# sonoff_DIY_3_gang_Dip_version-V_1_2.net
KiCad netlist of a schematic drawn in EAGLE
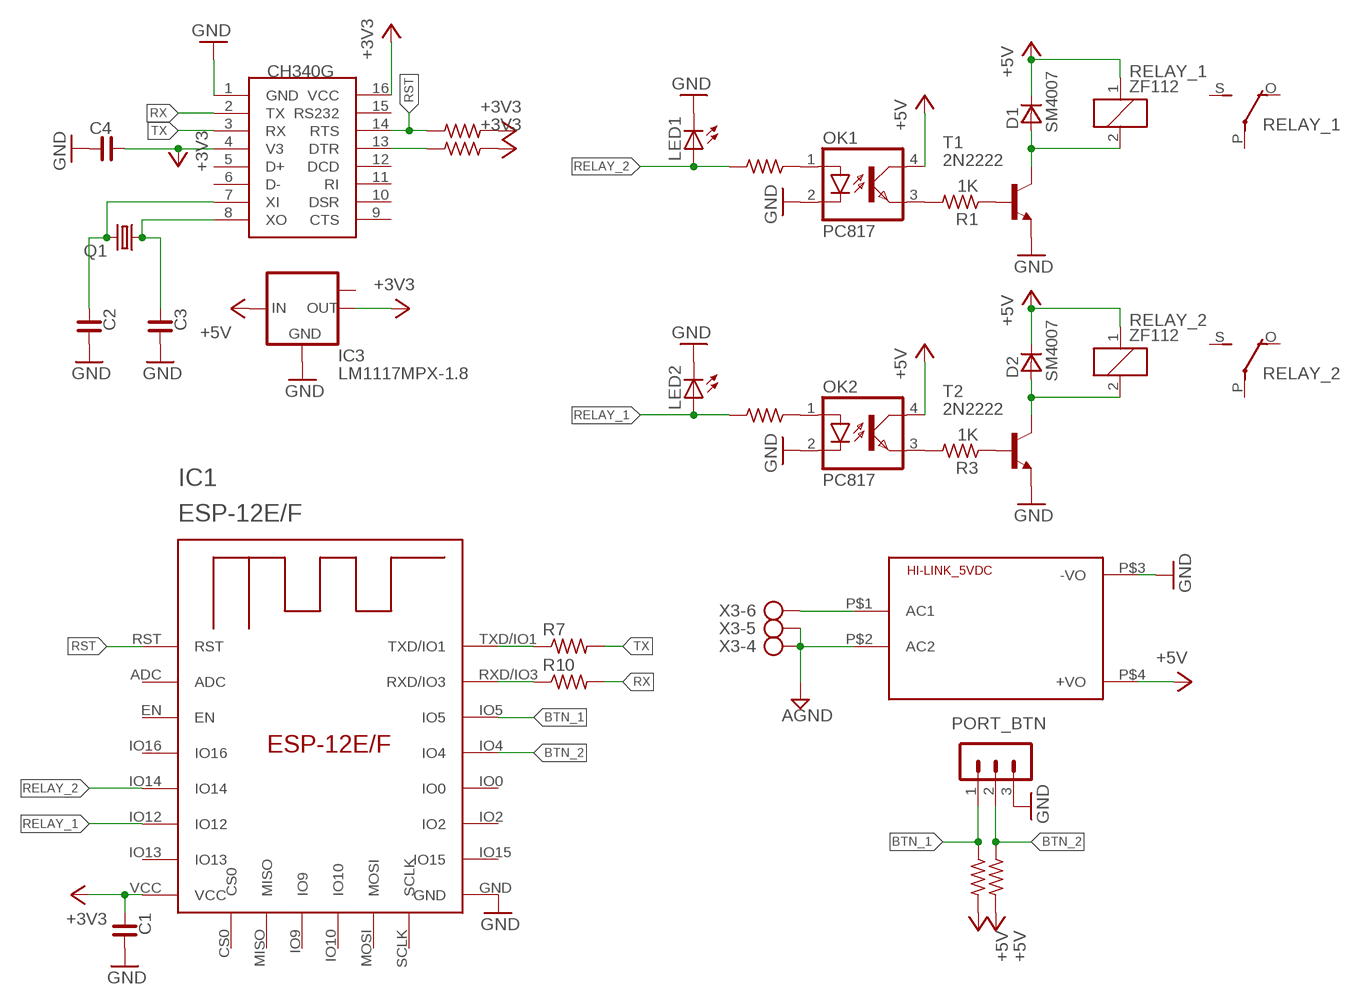
[diagram p0: schematic, sheet 1]

(export (version "E")
  (design (tool "Eeschema 10.0.6"))
  (components
    (comp (ref "C1")
      (value "C_0805")
      (footprint "eagle-import:C0805")
      (libsource (lib "eagle-import") (part "C_0805"))
    )
    (comp (ref "C2")
      (value "C_0805")
      (footprint "eagle-import:C0805")
      (libsource (lib "eagle-import") (part "C_0805"))
    )
    (comp (ref "C3")
      (value "C_0805")
      (footprint "eagle-import:C0805")
      (libsource (lib "eagle-import") (part "C_0805"))
    )
    (comp (ref "C4")
      (value "C_0805")
      (footprint "eagle-import:C0805")
      (libsource (lib "eagle-import") (part "C_0805"))
    )
    (comp (ref "D1")
      (value "SM4007")
      (footprint "eagle-import:MELF-MLL41")
      (libsource (lib "eagle-import") (part "SM4007"))
    )
    (comp (ref "D2")
      (value "SM4007")
      (footprint "eagle-import:MELF-MLL41")
      (libsource (lib "eagle-import") (part "SM4007"))
    )
    (comp (ref "HI-LINK_5VDC")
      (value "HLK-PM013W")
      (footprint "eagle-import:HLK-PM01")
      (libsource (lib "eagle-import") (part "HLK-PM013W"))
    )
    (comp (ref "IC1")
      (value "ESP-12E/F")
      (footprint "eagle-import:ESP-12E")
      (libsource (lib "eagle-import") (part "ESP-12E/F"))
    )
    (comp (ref "IC3")
      (value "LM1117MPX-1.8")
      (footprint "eagle-import:SOT223")
      (libsource (lib "eagle-import") (part "LM1117MPX-1.8"))
    )
    (comp (ref "LED1")
      (value "LED3MM")
      (footprint "eagle-import:LED3MM")
      (libsource (lib "eagle-import") (part "LED3MM"))
    )
    (comp (ref "LED2")
      (value "LED3MM")
      (footprint "eagle-import:LED3MM")
      (libsource (lib "eagle-import") (part "LED3MM"))
    )
    (comp (ref "OK1")
      (value "PC817")
      (footprint "eagle-import:DIL04")
      (fields (field (name "MPN") "PC817X4J000F"))
      (libsource (lib "eagle-import") (part "PC817"))
    )
    (comp (ref "OK2")
      (value "PC817")
      (footprint "eagle-import:DIL04")
      (fields (field (name "MPN") "PC817X4J000F"))
      (libsource (lib "eagle-import") (part "PC817"))
    )
    (comp (ref "PORT_BTN")
      (value "MA03-1")
      (footprint "eagle-import:MA03-1")
      (libsource (lib "eagle-import") (part "MA03-1"))
    )
    (comp (ref "Q1")
      (value "CRYSTALHC18U-V")
      (footprint "eagle-import:HC18U-V")
      (libsource (lib "eagle-import") (part "CRYSTALHC18U-V"))
    )
    (comp (ref "R1")
      (value "1K")
      (footprint "eagle-import:R0805")
      (libsource (lib "eagle-import") (part "R_0805"))
    )
    (comp (ref "R2")
      (value "1K")
      (footprint "eagle-import:R0805")
      (libsource (lib "eagle-import") (part "R_0805"))
    )
    (comp (ref "R3")
      (value "1K")
      (footprint "eagle-import:R0805")
      (libsource (lib "eagle-import") (part "R_0805"))
    )
    (comp (ref "R4")
      (value "1K")
      (footprint "eagle-import:R0805")
      (libsource (lib "eagle-import") (part "R_0805"))
    )
    (comp (ref "R5")
      (value "1K")
      (footprint "eagle-import:R0805")
      (libsource (lib "eagle-import") (part "R_0805"))
    )
    (comp (ref "R6")
      (value "1K")
      (footprint "eagle-import:R0805")
      (libsource (lib "eagle-import") (part "R_0805"))
    )
    (comp (ref "R7")
      (value "R-US_0207/10")
      (footprint "eagle-import:0207_10")
      (libsource (lib "eagle-import") (part "R-US_0207/10"))
    )
    (comp (ref "R8")
      (value "1K")
      (footprint "eagle-import:R0805")
      (libsource (lib "eagle-import") (part "R_0805"))
    )
    (comp (ref "R9")
      (value "1K")
      (footprint "eagle-import:R0805")
      (libsource (lib "eagle-import") (part "R_0805"))
    )
    (comp (ref "R10")
      (value "R-US_0207/10")
      (footprint "eagle-import:0207_10")
      (libsource (lib "eagle-import") (part "R-US_0207/10"))
    )
    (comp (ref "RELAY_1")
      (value "ZF112")
      (footprint "eagle-import:ZF112")
      (libsource (lib "eagle-import") (part "ZF112"))
    )
    (comp (ref "RELAY_2")
      (value "ZF112")
      (footprint "eagle-import:ZF112")
      (libsource (lib "eagle-import") (part "ZF112"))
    )
    (comp (ref "T1")
      (value "2N2222")
      (footprint "eagle-import:TO18")
      (libsource (lib "eagle-import") (part "2N2222"))
    )
    (comp (ref "T2")
      (value "2N2222")
      (footprint "eagle-import:TO18")
      (libsource (lib "eagle-import") (part "2N2222"))
    )
    (comp (ref "U$1")
      (value "CH340G")
      (footprint "eagle-import:SOIC16")
      (libsource (lib "eagle-import") (part "CH340G"))
    )
    (comp (ref "X3")
      (value "SMKDSP_1,5/6")
      (footprint "eagle-import:SMKDSP_1,5_6")
      (fields (field (name "MF") "FARNELL") (field (name "MPN") "1733619"))
      (libsource (lib "eagle-import") (part "SMKDSP_1,5/6"))
    )
  )
  (nets
    (net (code "1") (name "+3V3") (class "Default")
      (node (ref "C1") (pin "2") (pinfunction "2_2") (pintype "passive"))
      (node (ref "C4") (pin "1") (pinfunction "1_1") (pintype "passive"))
      (node (ref "IC1") (pin "VCC") (pinfunction "VCC_VCC") (pintype "power_in"))
      (node (ref "IC3") (pin "2") (pinfunction "OUT_2") (pintype "passive"))
      (node (ref "R8") (pin "1") (pinfunction "1_1") (pintype "passive"))
      (node (ref "R9") (pin "1") (pinfunction "1_1") (pintype "passive"))
      (node (ref "U$1") (pin "16") (pinfunction "VCC_16") (pintype "bidirectional"))
      (node (ref "U$1") (pin "4") (pinfunction "V3_4") (pintype "bidirectional"))
    )
    (net (code "2") (name "+5V") (class "Default")
      (node (ref "D1") (pin "C") (pinfunction "C_C") (pintype "passive"))
      (node (ref "D2") (pin "C") (pinfunction "C_C") (pintype "passive"))
      (node (ref "HI-LINK_5VDC") (pin "P$4") (pinfunction "+VO_P$4") (pintype "bidirectional"))
      (node (ref "IC3") (pin "3") (pinfunction "IN_3") (pintype "input"))
      (node (ref "OK1") (pin "4") (pinfunction "COL_4") (pintype "passive"))
      (node (ref "OK2") (pin "4") (pinfunction "COL_4") (pintype "passive"))
      (node (ref "R5") (pin "2") (pinfunction "2_2") (pintype "passive"))
      (node (ref "R6") (pin "2") (pinfunction "2_2") (pintype "passive"))
      (node (ref "RELAY_1") (pin "1") (pinfunction "1_1") (pintype "passive"))
      (node (ref "RELAY_2") (pin "1") (pinfunction "1_1") (pintype "passive"))
    )
    (net (code "3") (name "AGND") (class "Default")
      (node (ref "HI-LINK_5VDC") (pin "P$2") (pinfunction "AC2_P$2") (pintype "bidirectional"))
      (node (ref "X3") (pin "4") (pinfunction "KL_4") (pintype "passive"))
      (node (ref "X3") (pin "5") (pinfunction "KL_5") (pintype "passive"))
    )
    (net (code "4") (name "BTN_1") (class "Default")
      (node (ref "IC1") (pin "IO5") (pinfunction "IO5_IO5") (pintype "bidirectional"))
      (node (ref "PORT_BTN") (pin "1") (pinfunction "1_1") (pintype "passive"))
      (node (ref "R5") (pin "1") (pinfunction "1_1") (pintype "passive"))
    )
    (net (code "5") (name "BTN_2") (class "Default")
      (node (ref "IC1") (pin "IO4") (pinfunction "IO4_IO4") (pintype "bidirectional"))
      (node (ref "PORT_BTN") (pin "2") (pinfunction "2_2") (pintype "passive"))
      (node (ref "R6") (pin "1") (pinfunction "1_1") (pintype "passive"))
    )
    (net (code "6") (name "GND") (class "Default")
      (node (ref "C1") (pin "1") (pinfunction "1_1") (pintype "passive"))
      (node (ref "C2") (pin "1") (pinfunction "1_1") (pintype "passive"))
      (node (ref "C3") (pin "1") (pinfunction "1_1") (pintype "passive"))
      (node (ref "C4") (pin "2") (pinfunction "2_2") (pintype "passive"))
      (node (ref "HI-LINK_5VDC") (pin "P$3") (pinfunction "-VO_P$3") (pintype "bidirectional"))
      (node (ref "IC1") (pin "GND") (pinfunction "GND_GND") (pintype "power_in"))
      (node (ref "IC3") (pin "1") (pinfunction "GND_1") (pintype "input"))
      (node (ref "LED1") (pin "K") (pinfunction "C_K") (pintype "passive"))
      (node (ref "LED2") (pin "K") (pinfunction "C_K") (pintype "passive"))
      (node (ref "OK1") (pin "2") (pinfunction "C_2") (pintype "passive"))
      (node (ref "OK2") (pin "2") (pinfunction "C_2") (pintype "passive"))
      (node (ref "PORT_BTN") (pin "3") (pinfunction "3_3") (pintype "passive"))
      (node (ref "T1") (pin "1") (pinfunction "E_1") (pintype "passive"))
      (node (ref "T2") (pin "1") (pinfunction "E_1") (pintype "passive"))
      (node (ref "U$1") (pin "1") (pinfunction "GND_1") (pintype "bidirectional"))
    )
    (net (code "7") (name "Net-(HI-LINK_5VDC-AC1)") (class "Default")
      (node (ref "HI-LINK_5VDC") (pin "P$1") (pinfunction "AC1_P$1") (pintype "bidirectional"))
      (node (ref "X3") (pin "6") (pinfunction "KL_6") (pintype "passive"))
    )
    (net (code "8") (name "Net-(IC1-PadRXD{slash}IO3)") (class "Default")
      (node (ref "IC1") (pin "RXD/IO3") (pinfunction "RXD/IO3_RXD/IO3") (pintype "bidirectional"))
      (node (ref "R10") (pin "1") (pinfunction "1_1") (pintype "passive"))
    )
    (net (code "9") (name "Net-(IC1-PadTXD{slash}IO1)") (class "Default")
      (node (ref "IC1") (pin "TXD/IO1") (pinfunction "TXD/IO1_TXD/IO1") (pintype "bidirectional"))
      (node (ref "R7") (pin "1") (pinfunction "1_1") (pintype "passive"))
    )
    (net (code "10") (name "Net-(OK1-A)") (class "Default")
      (node (ref "OK1") (pin "1") (pinfunction "A_1") (pintype "passive"))
      (node (ref "R2") (pin "1") (pinfunction "1_1") (pintype "passive"))
    )
    (net (code "11") (name "Net-(OK1-EMIT)") (class "Default")
      (node (ref "OK1") (pin "3") (pinfunction "EMIT_3") (pintype "passive"))
      (node (ref "R1") (pin "2") (pinfunction "2_2") (pintype "passive"))
    )
    (net (code "12") (name "Net-(OK2-A)") (class "Default")
      (node (ref "OK2") (pin "1") (pinfunction "A_1") (pintype "passive"))
      (node (ref "R4") (pin "1") (pinfunction "1_1") (pintype "passive"))
    )
    (net (code "13") (name "Net-(OK2-EMIT)") (class "Default")
      (node (ref "OK2") (pin "3") (pinfunction "EMIT_3") (pintype "passive"))
      (node (ref "R3") (pin "2") (pinfunction "2_2") (pintype "passive"))
    )
    (net (code "14") (name "Net-(T1-B)") (class "Default")
      (node (ref "R1") (pin "1") (pinfunction "1_1") (pintype "passive"))
      (node (ref "T1") (pin "2") (pinfunction "B_2") (pintype "passive"))
    )
    (net (code "15") (name "Net-(T1-C)") (class "Default")
      (node (ref "D1") (pin "A") (pinfunction "A_A") (pintype "passive"))
      (node (ref "RELAY_1") (pin "2") (pinfunction "2_2") (pintype "passive"))
      (node (ref "T1") (pin "3") (pinfunction "C_3") (pintype "passive"))
    )
    (net (code "16") (name "Net-(T2-B)") (class "Default")
      (node (ref "R3") (pin "1") (pinfunction "1_1") (pintype "passive"))
      (node (ref "T2") (pin "2") (pinfunction "B_2") (pintype "passive"))
    )
    (net (code "17") (name "Net-(T2-C)") (class "Default")
      (node (ref "D2") (pin "A") (pinfunction "A_A") (pintype "passive"))
      (node (ref "RELAY_2") (pin "2") (pinfunction "2_2") (pintype "passive"))
      (node (ref "T2") (pin "3") (pinfunction "C_3") (pintype "passive"))
    )
    (net (code "18") (name "Net-(U$1-DTR)") (class "Default")
      (node (ref "R9") (pin "2") (pinfunction "2_2") (pintype "passive"))
      (node (ref "U$1") (pin "13") (pinfunction "DTR_13") (pintype "bidirectional"))
    )
    (net (code "19") (name "Net-(U$1-XI)") (class "Default")
      (node (ref "C2") (pin "2") (pinfunction "2_2") (pintype "passive"))
      (node (ref "Q1") (pin "2") (pinfunction "2_2") (pintype "passive"))
      (node (ref "U$1") (pin "7") (pinfunction "XI_7") (pintype "bidirectional"))
    )
    (net (code "20") (name "Net-(U$1-XO)") (class "Default")
      (node (ref "C3") (pin "2") (pinfunction "2_2") (pintype "passive"))
      (node (ref "Q1") (pin "1") (pinfunction "1_1") (pintype "passive"))
      (node (ref "U$1") (pin "8") (pinfunction "XO_8") (pintype "bidirectional"))
    )
    (net (code "21") (name "RELAY_1") (class "Default")
      (node (ref "IC1") (pin "IO12") (pinfunction "IO12_IO12") (pintype "bidirectional"))
      (node (ref "LED2") (pin "A") (pinfunction "A_A") (pintype "passive"))
      (node (ref "R4") (pin "2") (pinfunction "2_2") (pintype "passive"))
    )
    (net (code "22") (name "RELAY_2") (class "Default")
      (node (ref "IC1") (pin "IO14") (pinfunction "IO14_IO14") (pintype "bidirectional"))
      (node (ref "LED1") (pin "A") (pinfunction "A_A") (pintype "passive"))
      (node (ref "R2") (pin "2") (pinfunction "2_2") (pintype "passive"))
    )
    (net (code "23") (name "RST") (class "Default")
      (node (ref "IC1") (pin "RST") (pinfunction "RST_RST") (pintype "input"))
      (node (ref "R8") (pin "2") (pinfunction "2_2") (pintype "passive"))
      (node (ref "U$1") (pin "14") (pinfunction "RTS_14") (pintype "bidirectional"))
    )
    (net (code "24") (name "RX") (class "Default")
      (node (ref "R10") (pin "2") (pinfunction "2_2") (pintype "passive"))
      (node (ref "U$1") (pin "2") (pinfunction "TX_2") (pintype "bidirectional"))
    )
    (net (code "25") (name "TX") (class "Default")
      (node (ref "R7") (pin "2") (pinfunction "2_2") (pintype "passive"))
      (node (ref "U$1") (pin "3") (pinfunction "RX_3") (pintype "bidirectional"))
    )
    (net (code "26") (name "unconnected-(IC1-PadADC)") (class "Default")
      (node (ref "IC1") (pin "ADC") (pinfunction "ADC_ADC") (pintype "bidirectional"))
    )
    (net (code "27") (name "unconnected-(IC1-PadCS0)") (class "Default")
      (node (ref "IC1") (pin "CS0") (pinfunction "CS0_CS0") (pintype "bidirectional"))
    )
    (net (code "28") (name "unconnected-(IC1-PadEN)") (class "Default")
      (node (ref "IC1") (pin "EN") (pinfunction "EN_EN") (pintype "bidirectional"))
    )
    (net (code "29") (name "unconnected-(IC1-PadIO0)") (class "Default")
      (node (ref "IC1") (pin "IO0") (pinfunction "IO0_IO0") (pintype "bidirectional"))
    )
    (net (code "30") (name "unconnected-(IC1-PadIO2)") (class "Default")
      (node (ref "IC1") (pin "IO2") (pinfunction "IO2_IO2") (pintype "bidirectional"))
    )
    (net (code "31") (name "unconnected-(IC1-PadIO9)") (class "Default")
      (node (ref "IC1") (pin "IO9") (pinfunction "IO9_IO9") (pintype "bidirectional"))
    )
    (net (code "32") (name "unconnected-(IC1-PadIO10)") (class "Default")
      (node (ref "IC1") (pin "IO10") (pinfunction "IO10_IO10") (pintype "bidirectional"))
    )
    (net (code "33") (name "unconnected-(IC1-PadIO13)") (class "Default")
      (node (ref "IC1") (pin "IO13") (pinfunction "IO13_IO13") (pintype "bidirectional"))
    )
    (net (code "34") (name "unconnected-(IC1-PadIO15)") (class "Default")
      (node (ref "IC1") (pin "IO15") (pinfunction "IO15_IO15") (pintype "bidirectional"))
    )
    (net (code "35") (name "unconnected-(IC1-PadIO16)") (class "Default")
      (node (ref "IC1") (pin "IO16") (pinfunction "IO16_IO16") (pintype "bidirectional"))
    )
    (net (code "36") (name "unconnected-(IC1-PadMISO)") (class "Default")
      (node (ref "IC1") (pin "MISO") (pinfunction "MISO_MISO") (pintype "bidirectional"))
    )
    (net (code "37") (name "unconnected-(IC1-PadMOSI)") (class "Default")
      (node (ref "IC1") (pin "MOSI") (pinfunction "MOSI_MOSI") (pintype "bidirectional"))
    )
    (net (code "38") (name "unconnected-(IC1-PadSCLK)") (class "Default")
      (node (ref "IC1") (pin "SCLK") (pinfunction "SCLK_SCLK") (pintype "bidirectional"))
    )
    (net (code "39") (name "unconnected-(IC3-OUT1-PadTAB)") (class "Default")
      (node (ref "IC3") (pin "TAB") (pinfunction "OUT1_TAB") (pintype "passive"))
    )
    (net (code "40") (name "unconnected-(RELAY_1-PadO)") (class "Default")
      (node (ref "RELAY_1") (pin "O") (pinfunction "O_O") (pintype "passive"))
    )
    (net (code "41") (name "unconnected-(RELAY_1-PadP)") (class "Default")
      (node (ref "RELAY_1") (pin "P") (pinfunction "P_P") (pintype "passive"))
    )
    (net (code "42") (name "unconnected-(RELAY_1-PadS)") (class "Default")
      (node (ref "RELAY_1") (pin "S") (pinfunction "S_S") (pintype "passive"))
    )
    (net (code "43") (name "unconnected-(RELAY_2-PadO)") (class "Default")
      (node (ref "RELAY_2") (pin "O") (pinfunction "O_O") (pintype "passive"))
    )
    (net (code "44") (name "unconnected-(RELAY_2-PadP)") (class "Default")
      (node (ref "RELAY_2") (pin "P") (pinfunction "P_P") (pintype "passive"))
    )
    (net (code "45") (name "unconnected-(RELAY_2-PadS)") (class "Default")
      (node (ref "RELAY_2") (pin "S") (pinfunction "S_S") (pintype "passive"))
    )
    (net (code "46") (name "unconnected-(U$1-CTS-Pad9)") (class "Default")
      (node (ref "U$1") (pin "9") (pinfunction "CTS_9") (pintype "bidirectional"))
    )
    (net (code "47") (name "unconnected-(U$1-D+-Pad5)") (class "Default")
      (node (ref "U$1") (pin "5") (pinfunction "D+_5") (pintype "bidirectional"))
    )
    (net (code "48") (name "unconnected-(U$1-D--Pad6)") (class "Default")
      (node (ref "U$1") (pin "6") (pinfunction "D-_6") (pintype "bidirectional"))
    )
    (net (code "49") (name "unconnected-(U$1-DCD-Pad12)") (class "Default")
      (node (ref "U$1") (pin "12") (pinfunction "DCD_12") (pintype "bidirectional"))
    )
    (net (code "50") (name "unconnected-(U$1-DSR-Pad10)") (class "Default")
      (node (ref "U$1") (pin "10") (pinfunction "DSR_10") (pintype "bidirectional"))
    )
    (net (code "51") (name "unconnected-(U$1-RI-Pad11)") (class "Default")
      (node (ref "U$1") (pin "11") (pinfunction "RI_11") (pintype "bidirectional"))
    )
    (net (code "52") (name "unconnected-(U$1-RS232-Pad15)") (class "Default")
      (node (ref "U$1") (pin "15") (pinfunction "RS232_15") (pintype "bidirectional"))
    )
  )
)
